# HP_Filter.net
KiCad netlist of a schematic drawn in Altium Designer
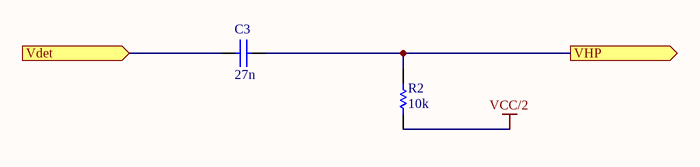
[diagram p0: HP Filter.SchDoc]

(export (version "E")
  (design (tool "Eeschema 10.0.6"))
  (components
    (comp (ref "C3")
      (value "27n")
      (footprint "ece-RAD0.2")
      (description "Capacitor Non Polarised Through Hole")
      (libsource (lib "ece components") (part "CAP"))
    )
    (comp (ref "R2")
      (value "10k")
      (footprint "ece-AXIAL0.4")
      (description "Resistor")
      (fields (field (name "PUBLISHER") "Altium Limited"))
      (libsource (lib "ece components") (part "Res1"))
    )
  )
  (nets
    (net (code "1") (name "/VHP") (class "Default")
      (node (ref "C3") (pin "2") (pinfunction "2_2") (pintype "passive"))
      (node (ref "R2") (pin "2") (pinfunction "2_2") (pintype "passive"))
    )
    (net (code "2") (name "/Vdet") (class "Default")
      (node (ref "C3") (pin "1") (pinfunction "1_1") (pintype "passive"))
    )
    (net (code "3") (name "VCC{slash}2") (class "Default")
      (node (ref "R2") (pin "1") (pinfunction "1_1") (pintype "passive"))
    )
  )
)
